# MotorControl.net
KiCad netlist of a schematic drawn in Altium Designer
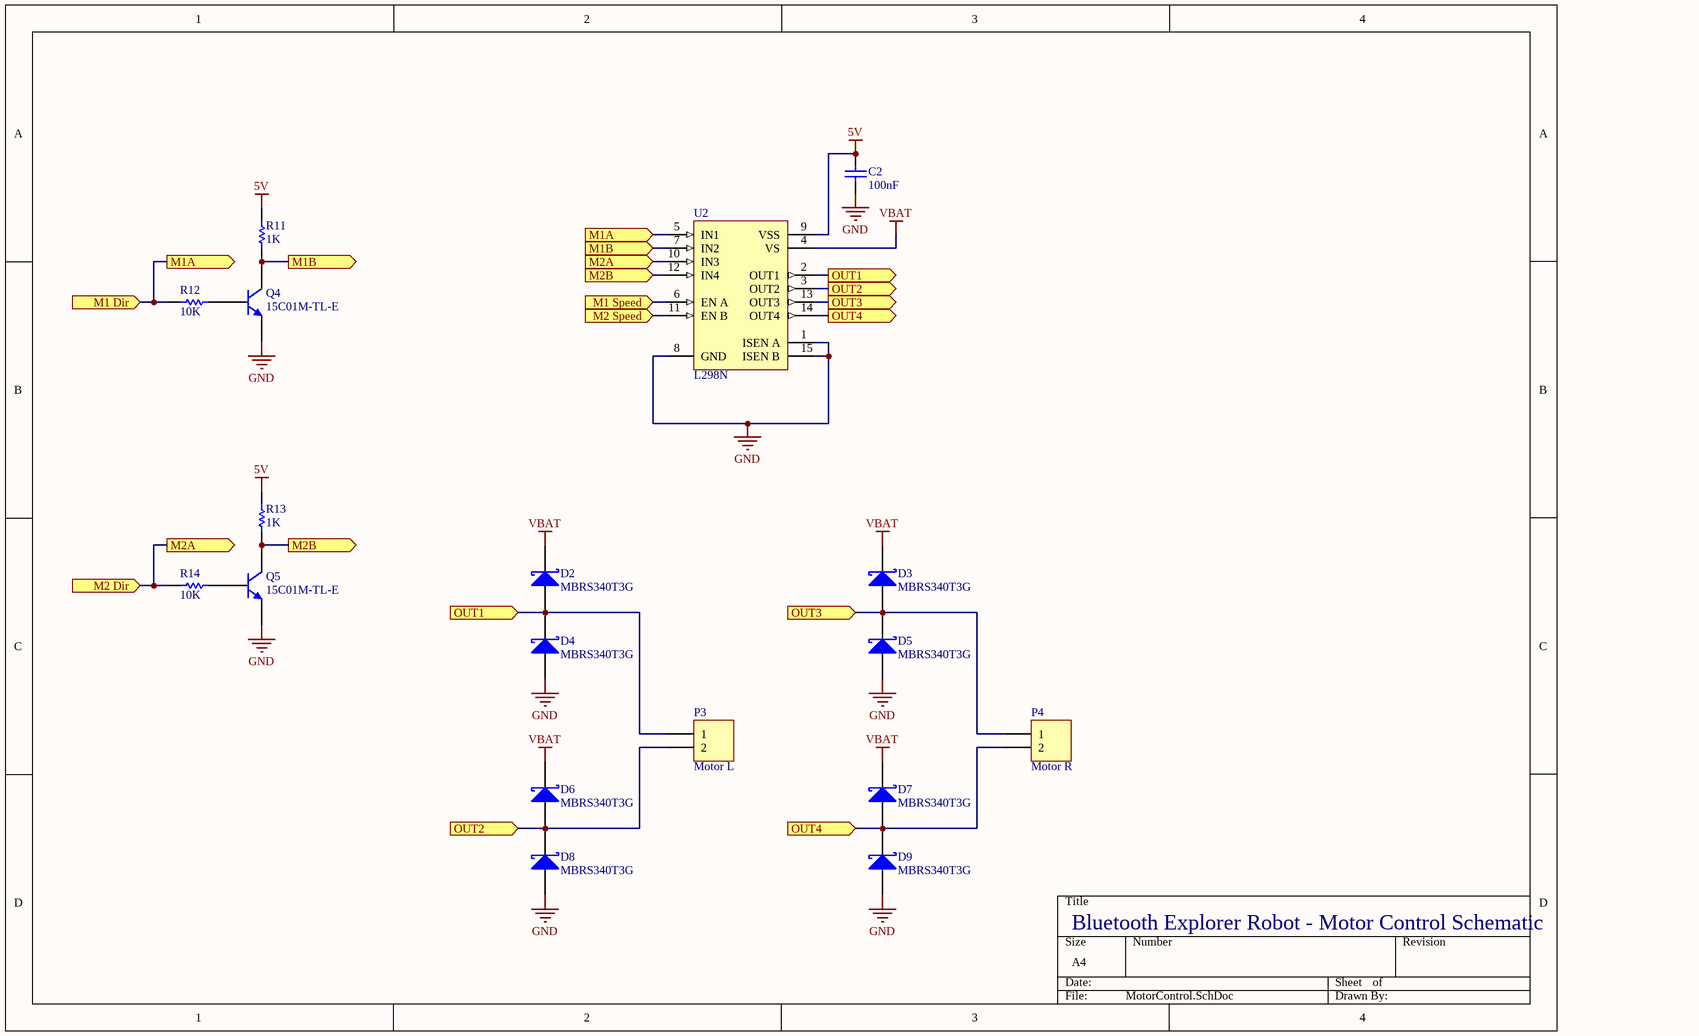
[diagram p0: MotorControl.SchDoc]

(export (version "E")
  (design (tool "Eeschema 10.0.6"))
  (components
    (comp (ref "C2")
      (value "100nF")
      (footprint "KEMET Chip Capacitor:0805")
      (description "Capacitor (Semiconductor SIM Model)")
      (fields (field (name "PUBLISHER") "Altium Limited"))
      (libsource (lib "Miscellaneous Devices") (part "Cap Semi"))
    )
    (comp (ref "D2")
      (value "MBRS340T3G")
      (footprint "SMC")
      (description "Schottky Diode")
      (fields (field (name "PUBLISHER") "Altium Limited"))
      (libsource (lib "Miscellaneous Devices") (part "D Schottky"))
    )
    (comp (ref "D3")
      (value "MBRS340T3G")
      (footprint "SMC")
      (description "Schottky Diode")
      (fields (field (name "PUBLISHER") "Altium Limited"))
      (libsource (lib "Miscellaneous Devices") (part "D Schottky"))
    )
    (comp (ref "D4")
      (value "MBRS340T3G")
      (footprint "SMC")
      (description "Schottky Diode")
      (fields (field (name "PUBLISHER") "Altium Limited"))
      (libsource (lib "Miscellaneous Devices") (part "D Schottky"))
    )
    (comp (ref "D5")
      (value "MBRS340T3G")
      (footprint "SMC")
      (description "Schottky Diode")
      (fields (field (name "PUBLISHER") "Altium Limited"))
      (libsource (lib "Miscellaneous Devices") (part "D Schottky"))
    )
    (comp (ref "D6")
      (value "MBRS340T3G")
      (footprint "SMC")
      (description "Schottky Diode")
      (fields (field (name "PUBLISHER") "Altium Limited"))
      (libsource (lib "Miscellaneous Devices") (part "D Schottky"))
    )
    (comp (ref "D7")
      (value "MBRS340T3G")
      (footprint "SMC")
      (description "Schottky Diode")
      (fields (field (name "PUBLISHER") "Altium Limited"))
      (libsource (lib "Miscellaneous Devices") (part "D Schottky"))
    )
    (comp (ref "D8")
      (value "MBRS340T3G")
      (footprint "SMC")
      (description "Schottky Diode")
      (fields (field (name "PUBLISHER") "Altium Limited"))
      (libsource (lib "Miscellaneous Devices") (part "D Schottky"))
    )
    (comp (ref "D9")
      (value "MBRS340T3G")
      (footprint "SMC")
      (description "Schottky Diode")
      (fields (field (name "PUBLISHER") "Altium Limited"))
      (libsource (lib "Miscellaneous Devices") (part "D Schottky"))
    )
    (comp (ref "P3")
      (value "Motor L")
      (footprint "PCB Screw Connector")
      (description "Header, 2-Pin")
      (fields (field (name "PUBLISHER") "Altium Limited"))
      (libsource (lib "Miscellaneous Connectors") (part "Header 2"))
    )
    (comp (ref "P4")
      (value "Motor R")
      (footprint "PCB Screw Connector")
      (description "Header, 2-Pin")
      (fields (field (name "PUBLISHER") "Altium Limited"))
      (libsource (lib "Miscellaneous Connectors") (part "Header 2"))
    )
    (comp (ref "Q4")
      (value "15C01M-TL-E")
      (footprint "SOT323")
      (description "NPN General Purpose Amplifier")
      (fields (field (name "PUBLISHER") "Altium Limited"))
      (libsource (lib "Miscellaneous Devices") (part "2N3904"))
    )
    (comp (ref "Q5")
      (value "15C01M-TL-E")
      (footprint "SOT323")
      (description "NPN General Purpose Amplifier")
      (fields (field (name "PUBLISHER") "Altium Limited"))
      (libsource (lib "Miscellaneous Devices") (part "2N3904"))
    )
    (comp (ref "R11")
      (value "1K")
      (footprint "2012[0805]")
      (description "Semiconductor Resistor")
      (fields (field (name "Comment") "Res Semi") (field (name "PUBLISHER") "Altium Limited"))
      (libsource (lib "Miscellaneous Devices") (part "Res Semi"))
    )
    (comp (ref "R12")
      (value "10K")
      (footprint "2012[0805]")
      (description "Semiconductor Resistor")
      (fields (field (name "Comment") "Res Semi") (field (name "PUBLISHER") "Altium Limited"))
      (libsource (lib "Miscellaneous Devices") (part "Res Semi"))
    )
    (comp (ref "R13")
      (value "1K")
      (footprint "2012[0805]")
      (description "Semiconductor Resistor")
      (fields (field (name "Comment") "Res Semi") (field (name "PUBLISHER") "Altium Limited"))
      (libsource (lib "Miscellaneous Devices") (part "Res Semi"))
    )
    (comp (ref "R14")
      (value "10K")
      (footprint "2012[0805]")
      (description "Semiconductor Resistor")
      (fields (field (name "Comment") "Res Semi") (field (name "PUBLISHER") "Altium Limited"))
      (libsource (lib "Miscellaneous Devices") (part "Res Semi"))
    )
    (comp (ref "U2")
      (value "L298N")
      (footprint "Multiwatt15V")
      (description "Dual Full Bridge Driver")
      (fields (field (name "PUBLISHER") "Altium Limited"))
      (libsource (lib "ST Interface DC Motor Controller") (part "L298N"))
    )
  )
  (nets
    (net (code "1") (name "/M1 Dir") (class "Default")
      (node (ref "R12") (pin "2") (pinfunction "2_2") (pintype "passive"))
      (node (ref "U2") (pin "5") (pinfunction "IN1_5") (pintype "input"))
    )
    (net (code "2") (name "/M1 Speed") (class "Default")
      (node (ref "U2") (pin "6") (pinfunction "EN_A_6") (pintype "input"))
    )
    (net (code "3") (name "/M1B") (class "Default")
      (node (ref "Q4") (pin "3") (pinfunction "C_3") (pintype "passive"))
      (node (ref "R11") (pin "1") (pinfunction "1_1") (pintype "passive"))
      (node (ref "U2") (pin "7") (pinfunction "IN2_7") (pintype "input"))
    )
    (net (code "4") (name "/M2 Dir") (class "Default")
      (node (ref "R14") (pin "2") (pinfunction "2_2") (pintype "passive"))
      (node (ref "U2") (pin "10") (pinfunction "IN3_10") (pintype "input"))
    )
    (net (code "5") (name "/M2 Speed") (class "Default")
      (node (ref "U2") (pin "11") (pinfunction "EN_B_11") (pintype "input"))
    )
    (net (code "6") (name "/M2B") (class "Default")
      (node (ref "Q5") (pin "3") (pinfunction "C_3") (pintype "passive"))
      (node (ref "R13") (pin "1") (pinfunction "1_1") (pintype "passive"))
      (node (ref "U2") (pin "12") (pinfunction "IN4_12") (pintype "input"))
    )
    (net (code "7") (name "/OUT1") (class "Default")
      (node (ref "D2") (pin "1") (pinfunction "A_1") (pintype "passive"))
      (node (ref "D4") (pin "2") (pinfunction "K_2") (pintype "passive"))
      (node (ref "P3") (pin "1") (pinfunction "1_1") (pintype "passive"))
      (node (ref "U2") (pin "2") (pinfunction "OUT1_2") (pintype "output"))
    )
    (net (code "8") (name "/OUT2") (class "Default")
      (node (ref "D6") (pin "1") (pinfunction "A_1") (pintype "passive"))
      (node (ref "D8") (pin "2") (pinfunction "K_2") (pintype "passive"))
      (node (ref "P3") (pin "2") (pinfunction "2_2") (pintype "passive"))
      (node (ref "U2") (pin "3") (pinfunction "OUT2_3") (pintype "output"))
    )
    (net (code "9") (name "/OUT3") (class "Default")
      (node (ref "D3") (pin "1") (pinfunction "A_1") (pintype "passive"))
      (node (ref "D5") (pin "2") (pinfunction "K_2") (pintype "passive"))
      (node (ref "P4") (pin "1") (pinfunction "1_1") (pintype "passive"))
      (node (ref "U2") (pin "13") (pinfunction "OUT3_13") (pintype "output"))
    )
    (net (code "10") (name "/OUT4") (class "Default")
      (node (ref "D7") (pin "1") (pinfunction "A_1") (pintype "passive"))
      (node (ref "D9") (pin "2") (pinfunction "K_2") (pintype "passive"))
      (node (ref "P4") (pin "2") (pinfunction "2_2") (pintype "passive"))
      (node (ref "U2") (pin "14") (pinfunction "OUT4_14") (pintype "output"))
    )
    (net (code "11") (name "5V") (class "Default")
      (node (ref "C2") (pin "1") (pinfunction "1_1") (pintype "passive"))
      (node (ref "R11") (pin "2") (pinfunction "2_2") (pintype "passive"))
      (node (ref "R13") (pin "2") (pinfunction "2_2") (pintype "passive"))
      (node (ref "U2") (pin "9") (pinfunction "VSS_9") (pintype "power_in"))
    )
    (net (code "12") (name "GND") (class "Default")
      (node (ref "C2") (pin "2") (pinfunction "2_2") (pintype "passive"))
      (node (ref "D4") (pin "1") (pinfunction "A_1") (pintype "passive"))
      (node (ref "D5") (pin "1") (pinfunction "A_1") (pintype "passive"))
      (node (ref "D8") (pin "1") (pinfunction "A_1") (pintype "passive"))
      (node (ref "D9") (pin "1") (pinfunction "A_1") (pintype "passive"))
      (node (ref "Q4") (pin "1") (pinfunction "E_1") (pintype "passive"))
      (node (ref "Q5") (pin "1") (pinfunction "E_1") (pintype "passive"))
      (node (ref "U2") (pin "1") (pinfunction "ISEN_A_1") (pintype "passive"))
      (node (ref "U2") (pin "15") (pinfunction "ISEN_B_15") (pintype "passive"))
      (node (ref "U2") (pin "8") (pinfunction "GND_8") (pintype "power_in"))
    )
    (net (code "13") (name "Net-(Q4-B)") (class "Default")
      (node (ref "Q4") (pin "2") (pinfunction "B_2") (pintype "passive"))
      (node (ref "R12") (pin "1") (pinfunction "1_1") (pintype "passive"))
    )
    (net (code "14") (name "Net-(Q5-B)") (class "Default")
      (node (ref "Q5") (pin "2") (pinfunction "B_2") (pintype "passive"))
      (node (ref "R14") (pin "1") (pinfunction "1_1") (pintype "passive"))
    )
    (net (code "15") (name "VBAT") (class "Default")
      (node (ref "D2") (pin "2") (pinfunction "K_2") (pintype "passive"))
      (node (ref "D3") (pin "2") (pinfunction "K_2") (pintype "passive"))
      (node (ref "D6") (pin "2") (pinfunction "K_2") (pintype "passive"))
      (node (ref "D7") (pin "2") (pinfunction "K_2") (pintype "passive"))
      (node (ref "U2") (pin "4") (pinfunction "VS_4") (pintype "power_in"))
    )
  )
)
